# powerdist2.net
KiCad netlist of a schematic drawn in EAGLE
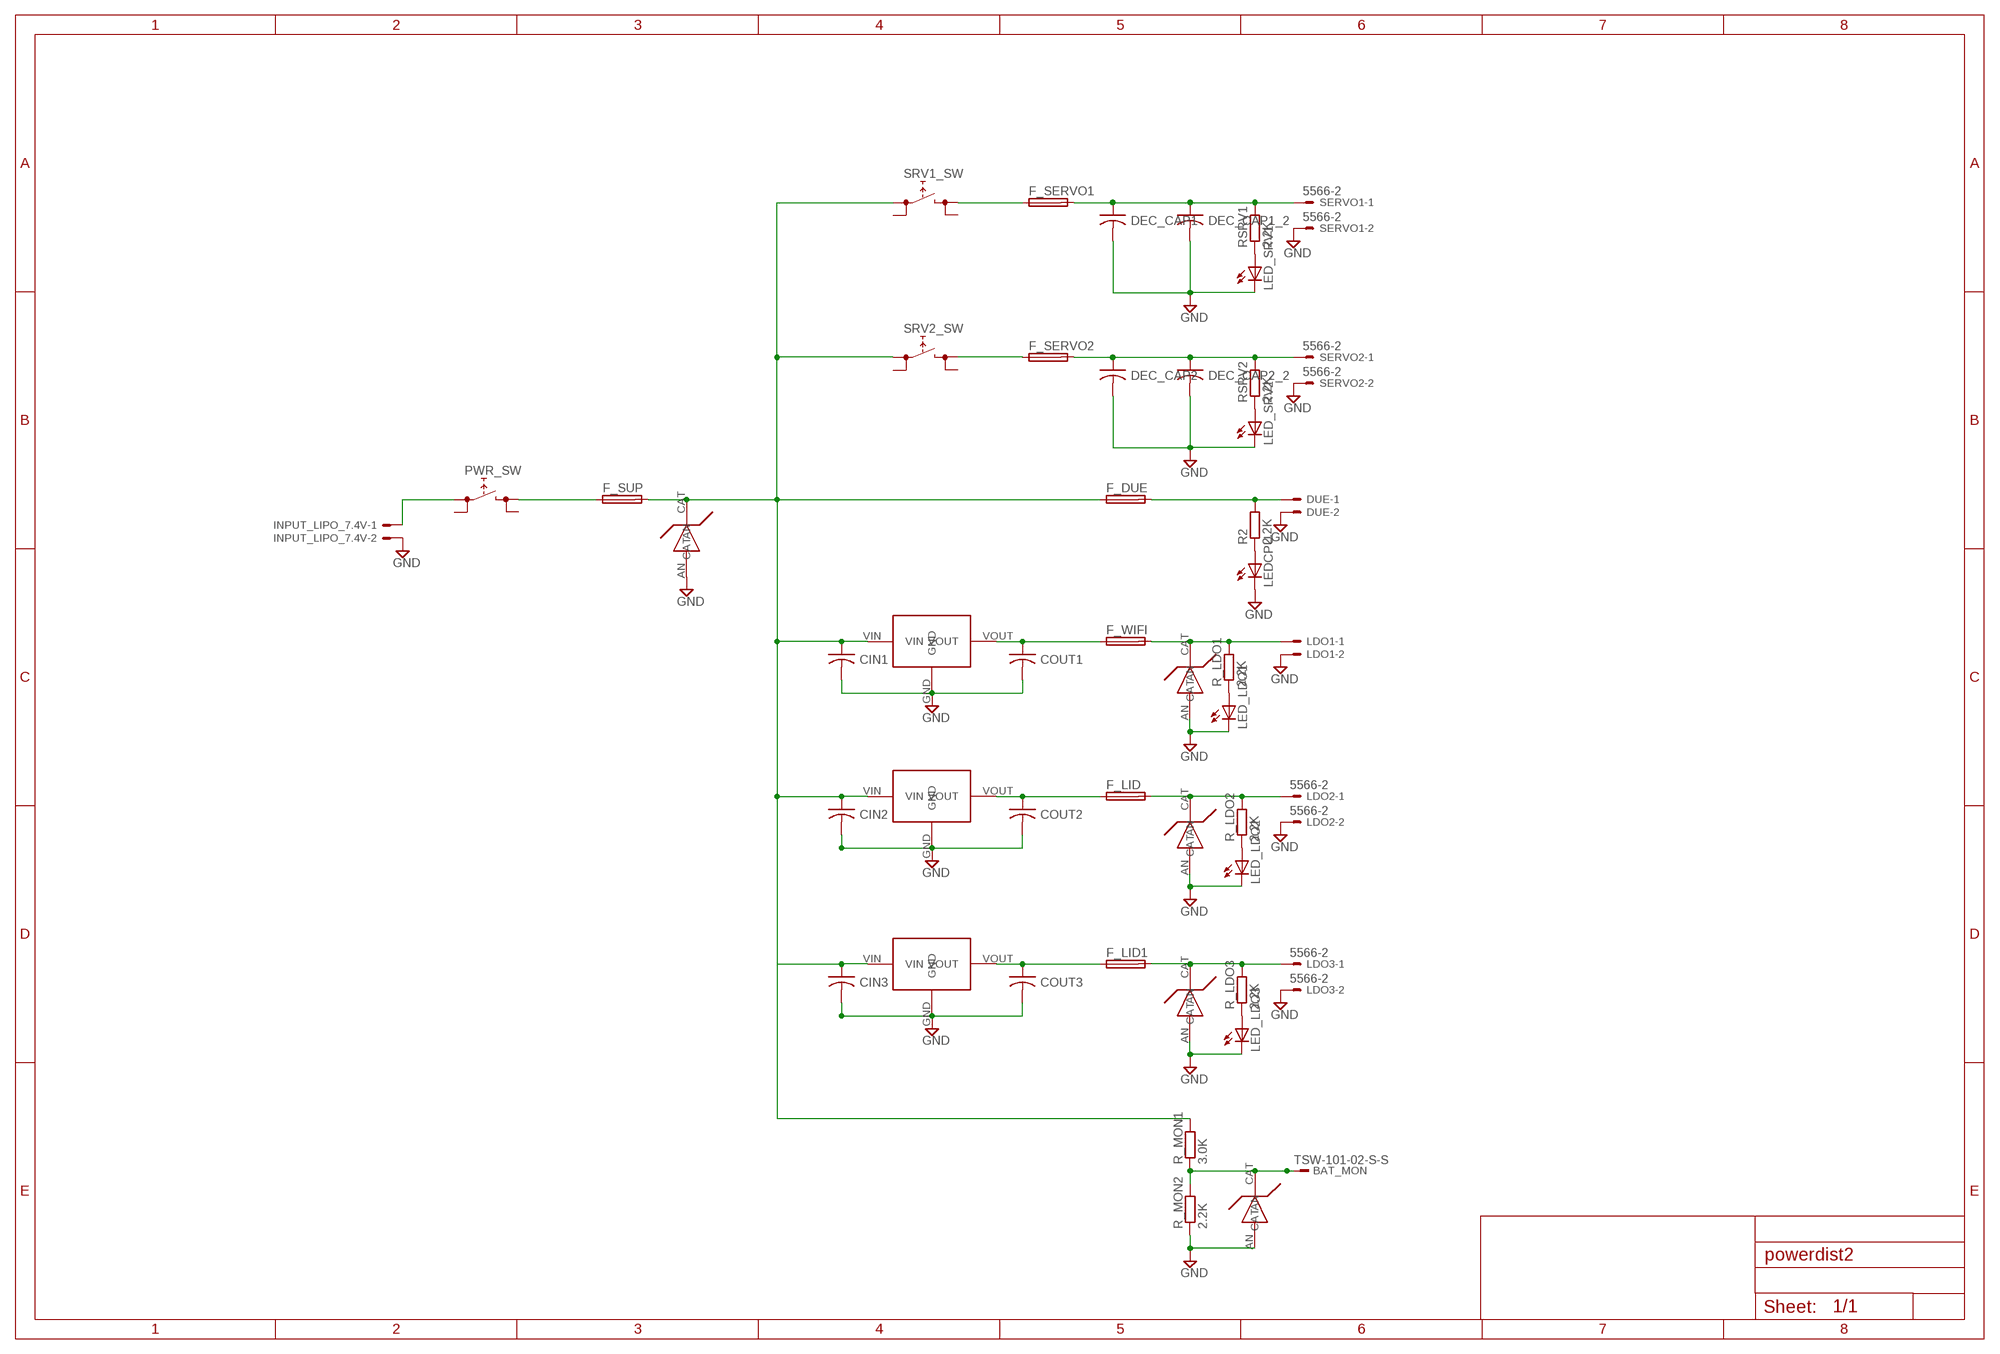
[diagram p0: schematic, sheet 1]

(export (version "E")
  (design (tool "Eeschema 10.0.6"))
  (components
    (comp (ref "BAT_MON")
      (value "TSW-101-02-S-S")
      (footprint "eagle-import:TSW-101-02-S-S")
      (libsource (lib "eagle-import") (part "TSW-101-02-S-S"))
    )
    (comp (ref "CIN1")
      (value "CAPACITORTH_CAP")
      (footprint "eagle-import:C025-025X050")
      (libsource (lib "eagle-import") (part "CAPACITORTH_CAP"))
    )
    (comp (ref "CIN2")
      (value "CAPACITORTH_CAP")
      (footprint "eagle-import:C025-025X050")
      (libsource (lib "eagle-import") (part "CAPACITORTH_CAP"))
    )
    (comp (ref "CIN3")
      (value "CAPACITORTH_CAP")
      (footprint "eagle-import:C025-025X050")
      (libsource (lib "eagle-import") (part "CAPACITORTH_CAP"))
    )
    (comp (ref "COUT1")
      (value "CAPACITORTH_CAP")
      (footprint "eagle-import:C025-025X050")
      (libsource (lib "eagle-import") (part "CAPACITORTH_CAP"))
    )
    (comp (ref "COUT2")
      (value "CAPACITORTH_CAP")
      (footprint "eagle-import:C025-025X050")
      (libsource (lib "eagle-import") (part "CAPACITORTH_CAP"))
    )
    (comp (ref "COUT3")
      (value "CAPACITORTH_CAP")
      (footprint "eagle-import:C025-025X050")
      (libsource (lib "eagle-import") (part "CAPACITORTH_CAP"))
    )
    (comp (ref "DEC_CAP1")
      (value "CAPACITORTH_CAP")
      (footprint "eagle-import:C025-025X050")
      (libsource (lib "eagle-import") (part "CAPACITORTH_CAP"))
    )
    (comp (ref "DEC_CAP1_2")
      (value "CAPACITORTH_CAP")
      (footprint "eagle-import:C025-025X050")
      (libsource (lib "eagle-import") (part "CAPACITORTH_CAP"))
    )
    (comp (ref "DEC_CAP2")
      (value "CAPACITORTH_CAP")
      (footprint "eagle-import:C025-025X050")
      (libsource (lib "eagle-import") (part "CAPACITORTH_CAP"))
    )
    (comp (ref "DEC_CAP2_2")
      (value "CAPACITORTH_CAP")
      (footprint "eagle-import:C025-025X050")
      (libsource (lib "eagle-import") (part "CAPACITORTH_CAP"))
    )
    (comp (ref "DUE")
      (value "C-GRID-02-70553")
      (footprint "eagle-import:70553-02")
      (libsource (lib "eagle-import") (part "C-GRID-02-70553"))
    )
    (comp (ref "F_DUE")
      (value "GSH15")
      (footprint "eagle-import:GSH15")
      (fields (field (name "MPN") "64900001039"))
      (libsource (lib "eagle-import") (part "GSH15"))
    )
    (comp (ref "F_LID")
      (value "GSH15")
      (footprint "eagle-import:GSH15")
      (fields (field (name "MPN") "64900001039"))
      (libsource (lib "eagle-import") (part "GSH15"))
    )
    (comp (ref "F_LID1")
      (value "GSH15")
      (footprint "eagle-import:GSH15")
      (fields (field (name "MPN") "64900001039"))
      (libsource (lib "eagle-import") (part "GSH15"))
    )
    (comp (ref "F_SERVO1")
      (value "GSH15")
      (footprint "eagle-import:GSH15")
      (fields (field (name "MPN") "64900001039"))
      (libsource (lib "eagle-import") (part "GSH15"))
    )
    (comp (ref "F_SERVO2")
      (value "GSH15")
      (footprint "eagle-import:GSH15")
      (fields (field (name "MPN") "64900001039"))
      (libsource (lib "eagle-import") (part "GSH15"))
    )
    (comp (ref "F_SUP")
      (value "GSH15")
      (footprint "eagle-import:GSH15")
      (fields (field (name "MPN") "64900001039"))
      (libsource (lib "eagle-import") (part "GSH15"))
    )
    (comp (ref "F_WIFI")
      (value "GSH15")
      (footprint "eagle-import:GSH15")
      (fields (field (name "MPN") "64900001039"))
      (libsource (lib "eagle-import") (part "GSH15"))
    )
    (comp (ref "INPUT_LIPO_7.4V")
      (value "22-23-2021")
      (footprint "eagle-import:22-23-2021")
      (fields (field (name "MF") "MOLEX"))
      (libsource (lib "eagle-import") (part "22-23-2021"))
    )
    (comp (ref "LDO1")
      (value "C-GRID-02-70553")
      (footprint "eagle-import:70553-02")
      (libsource (lib "eagle-import") (part "C-GRID-02-70553"))
    )
    (comp (ref "LDO2")
      (value "5566-2")
      (footprint "eagle-import:5566-2")
      (libsource (lib "eagle-import") (part "5566-2"))
    )
    (comp (ref "LDO3")
      (value "5566-2")
      (footprint "eagle-import:5566-2")
      (libsource (lib "eagle-import") (part "5566-2"))
    )
    (comp (ref "LEDCPU")
      (value "LEDCHIP-LED0805")
      (footprint "eagle-import:CHIP-LED0805")
      (libsource (lib "eagle-import") (part "LEDCHIP-LED0805"))
    )
    (comp (ref "LED_LDO1")
      (value "LEDCHIP-LED0805")
      (footprint "eagle-import:CHIP-LED0805")
      (libsource (lib "eagle-import") (part "LEDCHIP-LED0805"))
    )
    (comp (ref "LED_LDO2")
      (value "LEDCHIP-LED0805")
      (footprint "eagle-import:CHIP-LED0805")
      (libsource (lib "eagle-import") (part "LEDCHIP-LED0805"))
    )
    (comp (ref "LED_LDO3")
      (value "LEDCHIP-LED0805")
      (footprint "eagle-import:CHIP-LED0805")
      (libsource (lib "eagle-import") (part "LEDCHIP-LED0805"))
    )
    (comp (ref "LED_SRV1")
      (value "LEDCHIP-LED0805")
      (footprint "eagle-import:CHIP-LED0805")
      (libsource (lib "eagle-import") (part "LEDCHIP-LED0805"))
    )
    (comp (ref "LED_SRV2")
      (value "LEDCHIP-LED0805")
      (footprint "eagle-import:CHIP-LED0805")
      (libsource (lib "eagle-import") (part "LEDCHIP-LED0805"))
    )
    (comp (ref "LID12V1A")
      (value "MIC29150/29300/29500")
      (footprint "eagle-import:MIC29150_29300_29500")
      (libsource (lib "eagle-import") (part "MIC29150/29300/29500"))
    )
    (comp (ref "LID12V1A1")
      (value "MIC29150/29300/29500")
      (footprint "eagle-import:MIC29150_29300_29500")
      (libsource (lib "eagle-import") (part "MIC29150/29300/29500"))
    )
    (comp (ref "PWR_SW")
      (value "REKN")
      (footprint "eagle-import:REKN")
      (libsource (lib "eagle-import") (part "REKN"))
    )
    (comp (ref "R2")
      (value "2.2K")
      (footprint "eagle-import:R0402")
      (libsource (lib "eagle-import") (part "R-EU_R0402"))
    )
    (comp (ref "RSRV1")
      (value "2.2K")
      (footprint "eagle-import:R0402")
      (libsource (lib "eagle-import") (part "R-EU_R0402"))
    )
    (comp (ref "RSRV2")
      (value "2.2K")
      (footprint "eagle-import:R0402")
      (libsource (lib "eagle-import") (part "R-EU_R0402"))
    )
    (comp (ref "R_LDO1")
      (value "2.2K")
      (footprint "eagle-import:R0402")
      (libsource (lib "eagle-import") (part "R-EU_R0402"))
    )
    (comp (ref "R_LDO2")
      (value "2.2K")
      (footprint "eagle-import:R0402")
      (libsource (lib "eagle-import") (part "R-EU_R0402"))
    )
    (comp (ref "R_LDO3")
      (value "2.2K")
      (footprint "eagle-import:R0402")
      (libsource (lib "eagle-import") (part "R-EU_R0402"))
    )
    (comp (ref "R_MON1")
      (value "3.0K")
      (footprint "eagle-import:R0402")
      (libsource (lib "eagle-import") (part "R-EU_R0402"))
    )
    (comp (ref "R_MON2")
      (value "2.2K")
      (footprint "eagle-import:R0402")
      (libsource (lib "eagle-import") (part "R-EU_R0402"))
    )
    (comp (ref "SERVO1")
      (value "5566-2")
      (footprint "eagle-import:5566-2")
      (libsource (lib "eagle-import") (part "5566-2"))
    )
    (comp (ref "SERVO2")
      (value "5566-2")
      (footprint "eagle-import:5566-2")
      (libsource (lib "eagle-import") (part "5566-2"))
    )
    (comp (ref "SRV1_SW")
      (value "REKN")
      (footprint "eagle-import:REKN")
      (libsource (lib "eagle-import") (part "REKN"))
    )
    (comp (ref "SRV2_SW")
      (value "REKN")
      (footprint "eagle-import:REKN")
      (libsource (lib "eagle-import") (part "REKN"))
    )
    (comp (ref "TVS-MAIN")
      (value "26V")
      (footprint "eagle-import:TVS-SMAJ")
      (libsource (lib "eagle-import") (part "TVS-DIODE-SMAJ"))
    )
    (comp (ref "TVS-MAIN1")
      (value "16V")
      (footprint "eagle-import:TVS-SMAJ")
      (libsource (lib "eagle-import") (part "TVS-DIODE-SMAJ"))
    )
    (comp (ref "TVS-MAIN2")
      (value "5V")
      (footprint "eagle-import:TVS-SMAJ")
      (libsource (lib "eagle-import") (part "TVS-DIODE-SMAJ"))
    )
    (comp (ref "TVS-MAIN3")
      (value "16V")
      (footprint "eagle-import:TVS-SMAJ")
      (libsource (lib "eagle-import") (part "TVS-DIODE-SMAJ"))
    )
    (comp (ref "TVS_3.3")
      (value "16V")
      (footprint "eagle-import:TVS-SMAJ")
      (libsource (lib "eagle-import") (part "TVS-DIODE-SMAJ"))
    )
    (comp (ref "WIFI5V1A1")
      (value "MIC29150/29300/29500")
      (footprint "eagle-import:MIC29150_29300_29500")
      (libsource (lib "eagle-import") (part "MIC29150/29300/29500"))
    )
  )
  (nets
    (net (code "1") (name "GND") (class "Default")
      (node (ref "CIN1") (pin "2") (pinfunction "2_2") (pintype "bidirectional"))
      (node (ref "CIN2") (pin "2") (pinfunction "2_2") (pintype "bidirectional"))
      (node (ref "CIN3") (pin "2") (pinfunction "2_2") (pintype "bidirectional"))
      (node (ref "COUT1") (pin "2") (pinfunction "2_2") (pintype "bidirectional"))
      (node (ref "COUT2") (pin "2") (pinfunction "2_2") (pintype "bidirectional"))
      (node (ref "COUT3") (pin "2") (pinfunction "2_2") (pintype "bidirectional"))
      (node (ref "DEC_CAP1") (pin "2") (pinfunction "2_2") (pintype "bidirectional"))
      (node (ref "DEC_CAP1_2") (pin "2") (pinfunction "2_2") (pintype "bidirectional"))
      (node (ref "DEC_CAP2") (pin "2") (pinfunction "2_2") (pintype "bidirectional"))
      (node (ref "DEC_CAP2_2") (pin "2") (pinfunction "2_2") (pintype "bidirectional"))
      (node (ref "DUE") (pin "2") (pinfunction "S_2") (pintype "passive"))
      (node (ref "INPUT_LIPO_7.4V") (pin "2") (pinfunction "S_2") (pintype "passive"))
      (node (ref "LDO1") (pin "2") (pinfunction "S_2") (pintype "passive"))
      (node (ref "LDO2") (pin "2") (pinfunction "S_2") (pintype "passive"))
      (node (ref "LDO3") (pin "2") (pinfunction "S_2") (pintype "passive"))
      (node (ref "LEDCPU") (pin "C") (pinfunction "C_C") (pintype "passive"))
      (node (ref "LED_LDO1") (pin "C") (pinfunction "C_C") (pintype "passive"))
      (node (ref "LED_LDO2") (pin "C") (pinfunction "C_C") (pintype "passive"))
      (node (ref "LED_LDO3") (pin "C") (pinfunction "C_C") (pintype "passive"))
      (node (ref "LED_SRV1") (pin "C") (pinfunction "C_C") (pintype "passive"))
      (node (ref "LED_SRV2") (pin "C") (pinfunction "C_C") (pintype "passive"))
      (node (ref "LID12V1A") (pin "GND") (pinfunction "GND_GND") (pintype "bidirectional"))
      (node (ref "LID12V1A1") (pin "GND") (pinfunction "GND_GND") (pintype "bidirectional"))
      (node (ref "R_MON2") (pin "1") (pinfunction "1_1") (pintype "passive"))
      (node (ref "SERVO1") (pin "2") (pinfunction "S_2") (pintype "passive"))
      (node (ref "SERVO2") (pin "2") (pinfunction "S_2") (pintype "passive"))
      (node (ref "TVS-MAIN") (pin "AN") (pinfunction "AN_AN") (pintype "bidirectional"))
      (node (ref "TVS-MAIN1") (pin "AN") (pinfunction "AN_AN") (pintype "bidirectional"))
      (node (ref "TVS-MAIN2") (pin "AN") (pinfunction "AN_AN") (pintype "bidirectional"))
      (node (ref "TVS-MAIN3") (pin "AN") (pinfunction "AN_AN") (pintype "bidirectional"))
      (node (ref "TVS_3.3") (pin "AN") (pinfunction "AN_AN") (pintype "bidirectional"))
      (node (ref "WIFI5V1A1") (pin "GND") (pinfunction "GND_GND") (pintype "bidirectional"))
    )
    (net (code "2") (name "Net-(BAT_MON-Pad1)") (class "Default")
      (node (ref "BAT_MON") (pin "1") (pinfunction "1_1") (pintype "passive"))
      (node (ref "R_MON1") (pin "1") (pinfunction "1_1") (pintype "passive"))
      (node (ref "R_MON2") (pin "2") (pinfunction "2_2") (pintype "passive"))
      (node (ref "TVS_3.3") (pin "CAT") (pinfunction "CAT_CAT") (pintype "bidirectional"))
    )
    (net (code "3") (name "Net-(CIN1-Pad1)") (class "Default")
      (node (ref "CIN1") (pin "1") (pinfunction "1_1") (pintype "bidirectional"))
      (node (ref "CIN2") (pin "1") (pinfunction "1_1") (pintype "bidirectional"))
      (node (ref "F_DUE") (pin "1") (pinfunction "1_1") (pintype "passive"))
      (node (ref "F_SUP") (pin "2") (pinfunction "2_2") (pintype "passive"))
      (node (ref "LID12V1A") (pin "VIN") (pinfunction "VIN_VIN") (pintype "bidirectional"))
      (node (ref "R_MON1") (pin "2") (pinfunction "2_2") (pintype "passive"))
      (node (ref "SRV1_SW") (pin "0A") (pinfunction "0_0A") (pintype "passive"))
      (node (ref "SRV2_SW") (pin "0A") (pinfunction "0_0A") (pintype "passive"))
      (node (ref "TVS-MAIN") (pin "CAT") (pinfunction "CAT_CAT") (pintype "bidirectional"))
      (node (ref "WIFI5V1A1") (pin "VIN") (pinfunction "VIN_VIN") (pintype "bidirectional"))
    )
    (net (code "4") (name "Net-(CIN3-Pad1)") (class "Default")
      (node (ref "CIN3") (pin "1") (pinfunction "1_1") (pintype "bidirectional"))
      (node (ref "LID12V1A1") (pin "VIN") (pinfunction "VIN_VIN") (pintype "bidirectional"))
    )
    (net (code "5") (name "Net-(COUT1-Pad1)") (class "Default")
      (node (ref "COUT1") (pin "1") (pinfunction "1_1") (pintype "bidirectional"))
      (node (ref "F_WIFI") (pin "1") (pinfunction "1_1") (pintype "passive"))
      (node (ref "WIFI5V1A1") (pin "VOUT") (pinfunction "VOUT_VOUT") (pintype "bidirectional"))
    )
    (net (code "6") (name "Net-(COUT2-Pad1)") (class "Default")
      (node (ref "COUT2") (pin "1") (pinfunction "1_1") (pintype "bidirectional"))
      (node (ref "F_LID") (pin "1") (pinfunction "1_1") (pintype "passive"))
      (node (ref "LID12V1A") (pin "VOUT") (pinfunction "VOUT_VOUT") (pintype "bidirectional"))
    )
    (net (code "7") (name "Net-(COUT3-Pad1)") (class "Default")
      (node (ref "COUT3") (pin "1") (pinfunction "1_1") (pintype "bidirectional"))
      (node (ref "F_LID1") (pin "1") (pinfunction "1_1") (pintype "passive"))
      (node (ref "LID12V1A1") (pin "VOUT") (pinfunction "VOUT_VOUT") (pintype "bidirectional"))
    )
    (net (code "8") (name "Net-(DUEA-S)") (class "Default")
      (node (ref "DUE") (pin "1") (pinfunction "S_1") (pintype "passive"))
      (node (ref "F_DUE") (pin "2") (pinfunction "2_2") (pintype "passive"))
      (node (ref "R2") (pin "2") (pinfunction "2_2") (pintype "passive"))
    )
    (net (code "9") (name "Net-(F_SERVO1-Pad1)") (class "Default")
      (node (ref "F_SERVO1") (pin "1") (pinfunction "1_1") (pintype "passive"))
      (node (ref "SRV1_SW") (pin "1A") (pinfunction "1_1A") (pintype "passive"))
    )
    (net (code "10") (name "Net-(F_SERVO2-Pad1)") (class "Default")
      (node (ref "F_SERVO2") (pin "1") (pinfunction "1_1") (pintype "passive"))
      (node (ref "SRV2_SW") (pin "1A") (pinfunction "1_1A") (pintype "passive"))
    )
    (net (code "11") (name "Net-(F_SUP-Pad1)") (class "Default")
      (node (ref "F_SUP") (pin "1") (pinfunction "1_1") (pintype "passive"))
      (node (ref "PWR_SW") (pin "1A") (pinfunction "1_1A") (pintype "passive"))
    )
    (net (code "12") (name "Net-(INPUT_LIPO_7.4VA-S)") (class "Default")
      (node (ref "INPUT_LIPO_7.4V") (pin "1") (pinfunction "S_1") (pintype "passive"))
      (node (ref "PWR_SW") (pin "0A") (pinfunction "0_0A") (pintype "passive"))
    )
    (net (code "13") (name "Net-(LDO1A-S)") (class "Default")
      (node (ref "F_WIFI") (pin "2") (pinfunction "2_2") (pintype "passive"))
      (node (ref "LDO1") (pin "1") (pinfunction "S_1") (pintype "passive"))
      (node (ref "R_LDO1") (pin "2") (pinfunction "2_2") (pintype "passive"))
      (node (ref "TVS-MAIN2") (pin "CAT") (pinfunction "CAT_CAT") (pintype "bidirectional"))
    )
    (net (code "14") (name "Net-(LDO2A-S)") (class "Default")
      (node (ref "F_LID") (pin "2") (pinfunction "2_2") (pintype "passive"))
      (node (ref "LDO2") (pin "1") (pinfunction "S_1") (pintype "passive"))
      (node (ref "R_LDO2") (pin "2") (pinfunction "2_2") (pintype "passive"))
      (node (ref "TVS-MAIN3") (pin "CAT") (pinfunction "CAT_CAT") (pintype "bidirectional"))
    )
    (net (code "15") (name "Net-(LDO3A-S)") (class "Default")
      (node (ref "F_LID1") (pin "2") (pinfunction "2_2") (pintype "passive"))
      (node (ref "LDO3") (pin "1") (pinfunction "S_1") (pintype "passive"))
      (node (ref "R_LDO3") (pin "2") (pinfunction "2_2") (pintype "passive"))
      (node (ref "TVS-MAIN1") (pin "CAT") (pinfunction "CAT_CAT") (pintype "bidirectional"))
    )
    (net (code "16") (name "Net-(LEDCPU-PadA)") (class "Default")
      (node (ref "LEDCPU") (pin "A") (pinfunction "A_A") (pintype "passive"))
      (node (ref "R2") (pin "1") (pinfunction "1_1") (pintype "passive"))
    )
    (net (code "17") (name "Net-(LED_LDO1-PadA)") (class "Default")
      (node (ref "LED_LDO1") (pin "A") (pinfunction "A_A") (pintype "passive"))
      (node (ref "R_LDO1") (pin "1") (pinfunction "1_1") (pintype "passive"))
    )
    (net (code "18") (name "Net-(LED_LDO2-PadA)") (class "Default")
      (node (ref "LED_LDO2") (pin "A") (pinfunction "A_A") (pintype "passive"))
      (node (ref "R_LDO2") (pin "1") (pinfunction "1_1") (pintype "passive"))
    )
    (net (code "19") (name "Net-(LED_LDO3-PadA)") (class "Default")
      (node (ref "LED_LDO3") (pin "A") (pinfunction "A_A") (pintype "passive"))
      (node (ref "R_LDO3") (pin "1") (pinfunction "1_1") (pintype "passive"))
    )
    (net (code "20") (name "Net-(LED_SRV1-PadA)") (class "Default")
      (node (ref "LED_SRV1") (pin "A") (pinfunction "A_A") (pintype "passive"))
      (node (ref "RSRV1") (pin "1") (pinfunction "1_1") (pintype "passive"))
    )
    (net (code "21") (name "Net-(LED_SRV2-PadA)") (class "Default")
      (node (ref "LED_SRV2") (pin "A") (pinfunction "A_A") (pintype "passive"))
      (node (ref "RSRV2") (pin "1") (pinfunction "1_1") (pintype "passive"))
    )
    (net (code "22") (name "Net-(SERVO1A-S)") (class "Default")
      (node (ref "DEC_CAP1") (pin "1") (pinfunction "1_1") (pintype "bidirectional"))
      (node (ref "DEC_CAP1_2") (pin "1") (pinfunction "1_1") (pintype "bidirectional"))
      (node (ref "F_SERVO1") (pin "2") (pinfunction "2_2") (pintype "passive"))
      (node (ref "RSRV1") (pin "2") (pinfunction "2_2") (pintype "passive"))
      (node (ref "SERVO1") (pin "1") (pinfunction "S_1") (pintype "passive"))
    )
    (net (code "23") (name "Net-(SERVO2A-S)") (class "Default")
      (node (ref "DEC_CAP2") (pin "1") (pinfunction "1_1") (pintype "bidirectional"))
      (node (ref "DEC_CAP2_2") (pin "1") (pinfunction "1_1") (pintype "bidirectional"))
      (node (ref "F_SERVO2") (pin "2") (pinfunction "2_2") (pintype "passive"))
      (node (ref "RSRV2") (pin "2") (pinfunction "2_2") (pintype "passive"))
      (node (ref "SERVO2") (pin "1") (pinfunction "S_1") (pintype "passive"))
    )
    (net (code "24") (name "unconnected-(PWR_SW-0-Pad0B)") (class "Default")
      (node (ref "PWR_SW") (pin "0B") (pinfunction "0_0B") (pintype "passive"))
    )
    (net (code "25") (name "unconnected-(PWR_SW-1-Pad1B)") (class "Default")
      (node (ref "PWR_SW") (pin "1B") (pinfunction "1_1B") (pintype "passive"))
    )
    (net (code "26") (name "unconnected-(SRV1_SW-0-Pad0B)") (class "Default")
      (node (ref "SRV1_SW") (pin "0B") (pinfunction "0_0B") (pintype "passive"))
    )
    (net (code "27") (name "unconnected-(SRV1_SW-1-Pad1B)") (class "Default")
      (node (ref "SRV1_SW") (pin "1B") (pinfunction "1_1B") (pintype "passive"))
    )
    (net (code "28") (name "unconnected-(SRV2_SW-0-Pad0B)") (class "Default")
      (node (ref "SRV2_SW") (pin "0B") (pinfunction "0_0B") (pintype "passive"))
    )
    (net (code "29") (name "unconnected-(SRV2_SW-1-Pad1B)") (class "Default")
      (node (ref "SRV2_SW") (pin "1B") (pinfunction "1_1B") (pintype "passive"))
    )
  )
)
